# Camera.net
KiCad netlist of a schematic drawn in EAGLE
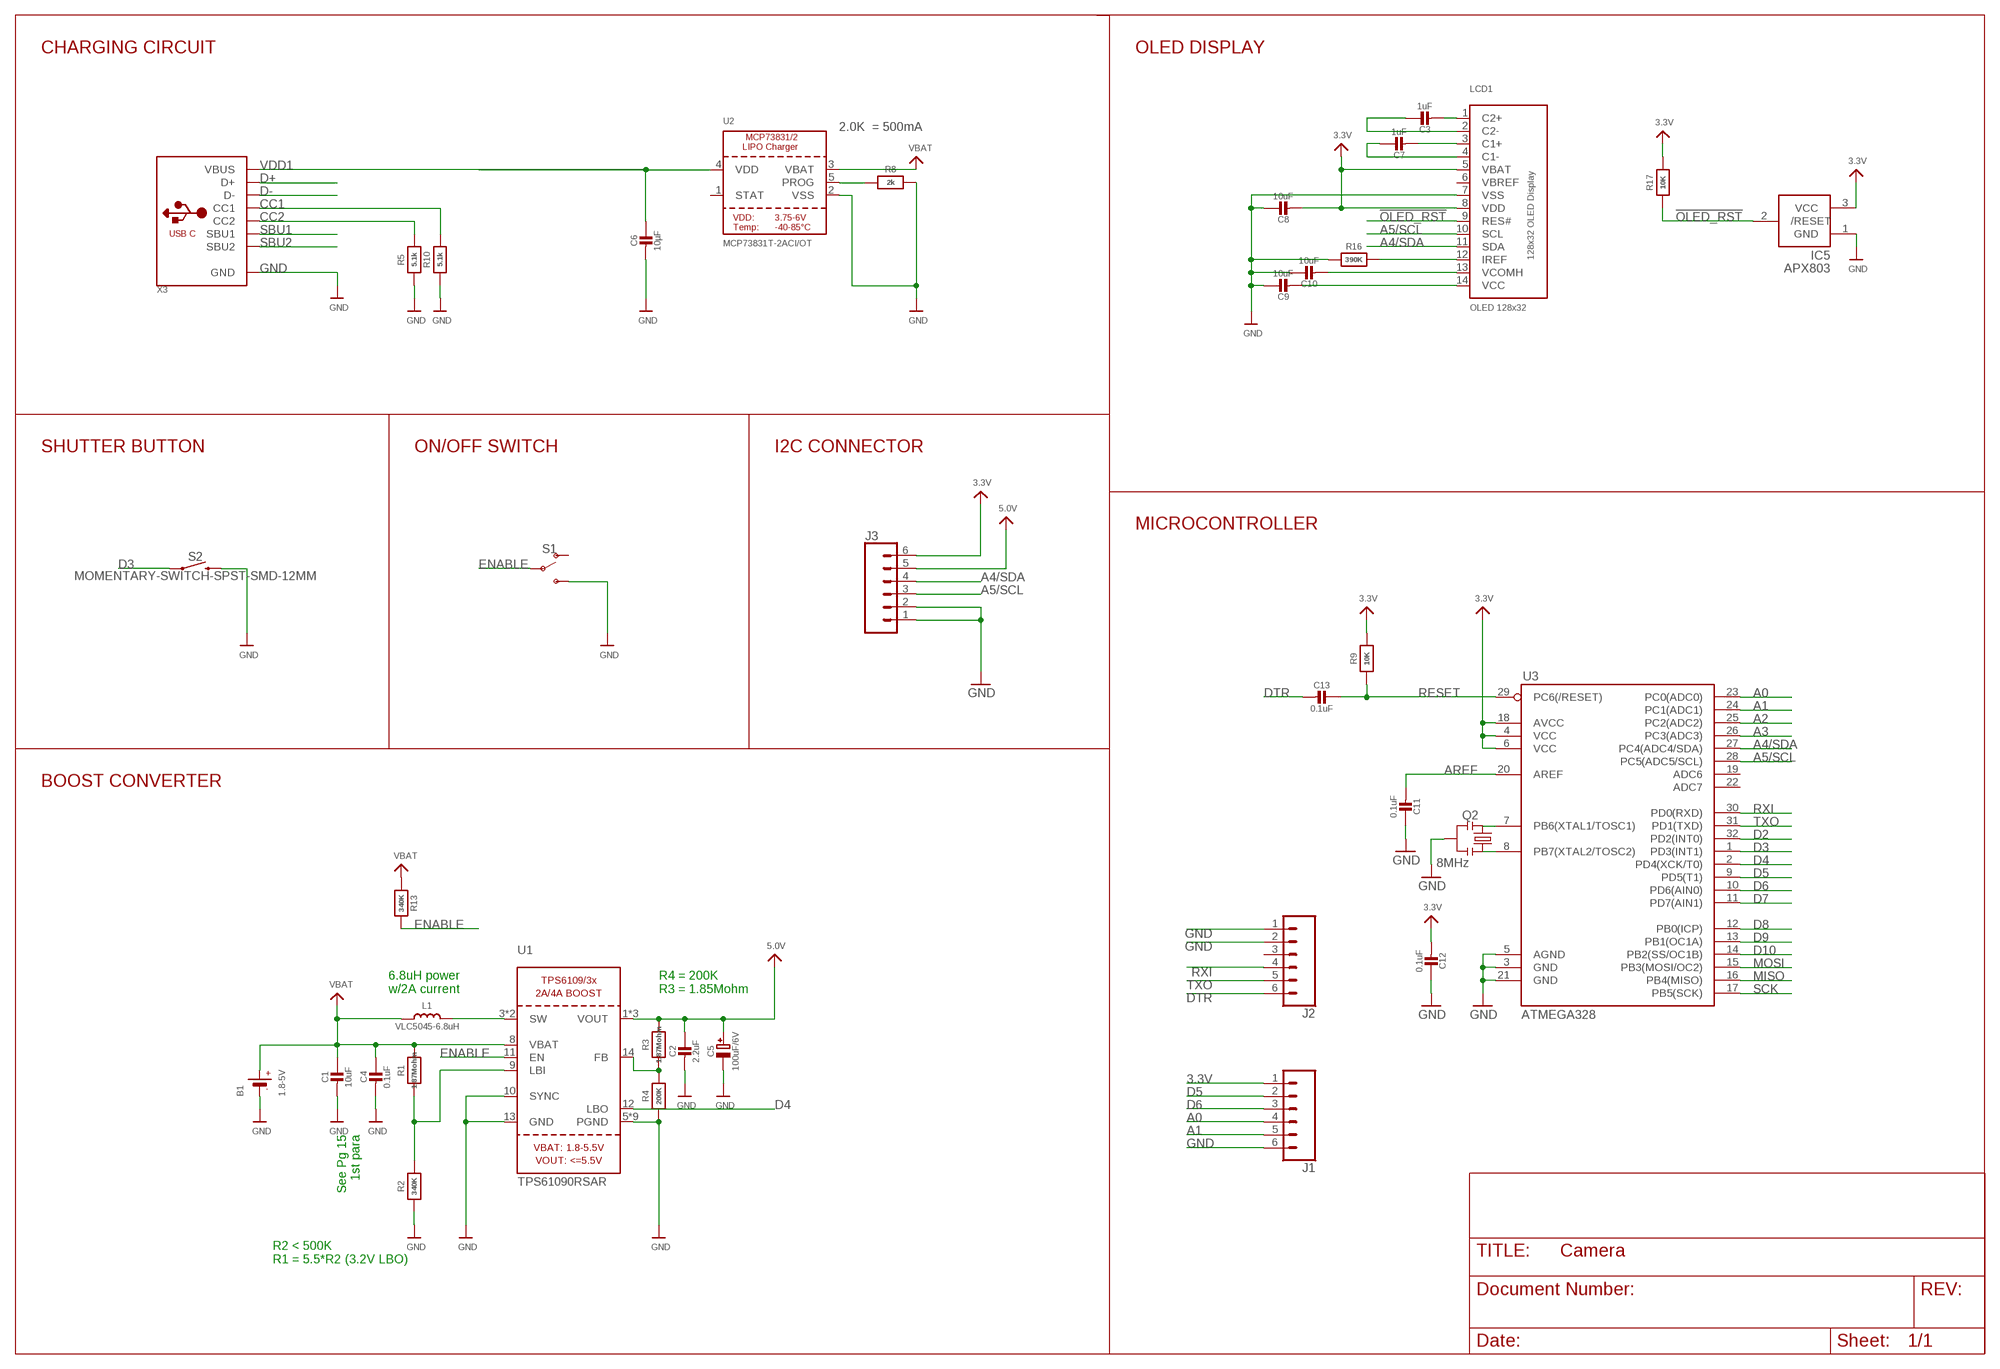
[diagram p0: schematic, sheet 1]

(export (version "E")
  (design (tool "Eeschema 10.0.6"))
  (components
    (comp (ref "B1")
      (value "1.8-5V")
      (footprint "eagle-import:JSTPH2")
      (libsource (lib "eagle-import") (part "BATTERY"))
    )
    (comp (ref "C1")
      (value "10uF")
      (footprint "eagle-import:0805-NO")
      (libsource (lib "eagle-import") (part "CAP_CERAMIC0805-NOOUTLINE"))
    )
    (comp (ref "C2")
      (value "2.2uF")
      (footprint "eagle-import:0805-NO")
      (libsource (lib "eagle-import") (part "CAP_CERAMIC0805-NOOUTLINE"))
    )
    (comp (ref "C3")
      (value "1uF")
      (footprint "eagle-import:0805-NO")
      (libsource (lib "eagle-import") (part "CAP_CERAMIC0805-NOOUTLINE"))
    )
    (comp (ref "C4")
      (value "0.1uF")
      (footprint "eagle-import:0805-NO")
      (libsource (lib "eagle-import") (part "CAP_CERAMIC0805-NOOUTLINE"))
    )
    (comp (ref "C5")
      (value "100uF/6V")
      (footprint "eagle-import:EIA3528-21_B-R")
      (libsource (lib "eagle-import") (part "CAP_TANTALUMB/3528_REFLOW"))
    )
    (comp (ref "C6")
      (value "10µF")
      (footprint "eagle-import:0805-NO")
      (libsource (lib "eagle-import") (part "CAP_CERAMIC0805-NOOUTLINE"))
    )
    (comp (ref "C7")
      (value "1uF")
      (footprint "eagle-import:0805-NO")
      (libsource (lib "eagle-import") (part "CAP_CERAMIC0805-NOOUTLINE"))
    )
    (comp (ref "C8")
      (value "10uF")
      (footprint "eagle-import:0805-NO")
      (libsource (lib "eagle-import") (part "CAP_CERAMIC0805-NOOUTLINE"))
    )
    (comp (ref "C9")
      (value "10uF")
      (footprint "eagle-import:0805-NO")
      (libsource (lib "eagle-import") (part "CAP_CERAMIC0805-NOOUTLINE"))
    )
    (comp (ref "C10")
      (value "10uF")
      (footprint "eagle-import:0805-NO")
      (libsource (lib "eagle-import") (part "CAP_CERAMIC0805-NOOUTLINE"))
    )
    (comp (ref "C11")
      (value "0.1uF")
      (footprint "eagle-import:0805-NO")
      (libsource (lib "eagle-import") (part "CAP_CERAMIC0805-NOOUTLINE"))
    )
    (comp (ref "C12")
      (value "0.1uF")
      (footprint "eagle-import:0805-NO")
      (libsource (lib "eagle-import") (part "CAP_CERAMIC0805-NOOUTLINE"))
    )
    (comp (ref "C13")
      (value "0.1uF")
      (footprint "eagle-import:0805-NO")
      (libsource (lib "eagle-import") (part "CAP_CERAMIC0805-NOOUTLINE"))
    )
    (comp (ref "IC5")
      (value "APX803")
      (footprint "eagle-import:SOT23")
      (libsource (lib "eagle-import") (part "AXP083-SAG"))
    )
    (comp (ref "J1")
      (value "CONN_06SMD-FEMALE-V2")
      (footprint "eagle-import:1X06-SMD-FEMALE")
      (libsource (lib "eagle-import") (part "CONN_06SMD-FEMALE-V2"))
    )
    (comp (ref "J2")
      (value "CONN_06SMD-FEMALE-V2")
      (footprint "eagle-import:1X06-SMD-FEMALE")
      (libsource (lib "eagle-import") (part "CONN_06SMD-FEMALE-V2"))
    )
    (comp (ref "J3")
      (value "CONN_06SMD-FEMALE-V2")
      (footprint "eagle-import:1X06-SMD-FEMALE")
      (libsource (lib "eagle-import") (part "CONN_06SMD-FEMALE-V2"))
    )
    (comp (ref "L1")
      (value "VLC5045-6.8uH")
      (footprint "eagle-import:INDUCTOR_5X5MM_TDK_VLC5045")
      (libsource (lib "eagle-import") (part "INDUCTORTDK_VLC5045"))
    )
    (comp (ref "LCD1")
      (value "OLED 128x32")
      (footprint "eagle-import:UG-2832HSWEG02_WRAPUNDER")
      (libsource (lib "eagle-import") (part "DISP_OLED_UG-2832HSWEG02"))
    )
    (comp (ref "Q2")
      (value "8MHz")
      (footprint "eagle-import:RESONATOR-SMD")
      (libsource (lib "eagle-import") (part "RESONATORSMD"))
    )
    (comp (ref "R1")
      (value "1.87Mohm")
      (footprint "eagle-import:0805-NO")
      (libsource (lib "eagle-import") (part "RESISTOR0805_NOOUTLINE"))
    )
    (comp (ref "R2")
      (value "340K")
      (footprint "eagle-import:0805-NO")
      (libsource (lib "eagle-import") (part "RESISTOR0805_NOOUTLINE"))
    )
    (comp (ref "R3")
      (value "1.87Mohm")
      (footprint "eagle-import:0805-NO")
      (libsource (lib "eagle-import") (part "RESISTOR0805_NOOUTLINE"))
    )
    (comp (ref "R4")
      (value "200K")
      (footprint "eagle-import:0805-NO")
      (libsource (lib "eagle-import") (part "RESISTOR0805_NOOUTLINE"))
    )
    (comp (ref "R5")
      (value "5.1k")
      (footprint "eagle-import:0805-NO")
      (libsource (lib "eagle-import") (part "RESISTOR0805_NOOUTLINE"))
    )
    (comp (ref "R8")
      (value "2k")
      (footprint "eagle-import:0805-NO")
      (libsource (lib "eagle-import") (part "RESISTOR0805_NOOUTLINE"))
    )
    (comp (ref "R9")
      (value "10K")
      (footprint "eagle-import:0805-NO")
      (libsource (lib "eagle-import") (part "RESISTOR0805_NOOUTLINE"))
    )
    (comp (ref "R10")
      (value "5.1k")
      (footprint "eagle-import:0805-NO")
      (libsource (lib "eagle-import") (part "RESISTOR0805_NOOUTLINE"))
    )
    (comp (ref "R13")
      (value "340K")
      (footprint "eagle-import:0805-NO")
      (libsource (lib "eagle-import") (part "RESISTOR0805_NOOUTLINE"))
    )
    (comp (ref "R16")
      (value "390K")
      (footprint "eagle-import:0805-NO")
      (libsource (lib "eagle-import") (part "RESISTOR0805_NOOUTLINE"))
    )
    (comp (ref "R17")
      (value "10K")
      (footprint "eagle-import:0805-NO")
      (libsource (lib "eagle-import") (part "RESISTOR0805_NOOUTLINE"))
    )
    (comp (ref "S1")
      (value "SWITCH-SPDT-SMD-RIGHT-ANGLE")
      (footprint "eagle-import:SWITCH_SPST_SMD_A")
      (libsource (lib "eagle-import") (part "SWITCH-SPDT-SMD-RIGHT-ANGLE"))
    )
    (comp (ref "S2")
      (value "MOMENTARY-SWITCH-SPST-SMD-12MM")
      (footprint "eagle-import:TACTILE_SWITCH_SMD_12MM")
      (libsource (lib "eagle-import") (part "MOMENTARY-SWITCH-SPST-SMD-12MM"))
    )
    (comp (ref "U1")
      (value "TPS61090RSAR")
      (footprint "eagle-import:PVQFN-16")
      (libsource (lib "eagle-import") (part "VREG_TPS6103X"))
    )
    (comp (ref "U2")
      (value "MCP73831T-2ACI/OT")
      (footprint "eagle-import:SOT23-5")
      (libsource (lib "eagle-import") (part "MCP73831/2"))
    )
    (comp (ref "U3")
      (value "ATMEGA328")
      (footprint "eagle-import:TQFP32-08")
      (libsource (lib "eagle-import") (part "ATMEGA168"))
    )
    (comp (ref "X3")
      (value "USB_C")
      (footprint "eagle-import:USB_C_CUSB31-CFM2AX-01-X")
      (libsource (lib "eagle-import") (part "USB_C"))
    )
  )
  (nets
    (net (code "1") (name "/A0") (class "Default")
      (node (ref "J1") (pin "4") (pinfunction "4_4") (pintype "passive"))
      (node (ref "U3") (pin "23") (pinfunction "PC0(ADC0)_23") (pintype "bidirectional"))
    )
    (net (code "2") (name "/A1") (class "Default")
      (node (ref "J1") (pin "5") (pinfunction "5_5") (pintype "passive"))
      (node (ref "U3") (pin "24") (pinfunction "PC1(ADC1)_24") (pintype "bidirectional"))
    )
    (net (code "3") (name "/A2") (class "Default")
      (node (ref "U3") (pin "25") (pinfunction "PC2(ADC2)_25") (pintype "bidirectional"))
    )
    (net (code "4") (name "/A3") (class "Default")
      (node (ref "U3") (pin "26") (pinfunction "PC3(ADC3)_26") (pintype "bidirectional"))
    )
    (net (code "5") (name "/A4{slash}SDA") (class "Default")
      (node (ref "J3") (pin "4") (pinfunction "4_4") (pintype "passive"))
      (node (ref "LCD1") (pin "11") (pinfunction "SDA_11") (pintype "bidirectional"))
      (node (ref "U3") (pin "27") (pinfunction "PC4(ADC4/SDA)_27") (pintype "bidirectional"))
    )
    (net (code "6") (name "/A5{slash}SCL") (class "Default")
      (node (ref "J3") (pin "3") (pinfunction "3_3") (pintype "passive"))
      (node (ref "LCD1") (pin "10") (pinfunction "SCL_10") (pintype "bidirectional"))
      (node (ref "U3") (pin "28") (pinfunction "PC5(ADC5/SCL)_28") (pintype "bidirectional"))
    )
    (net (code "7") (name "/AREF") (class "Default")
      (node (ref "C11") (pin "2") (pinfunction "2_2") (pintype "passive"))
      (node (ref "U3") (pin "20") (pinfunction "AREF_20") (pintype "bidirectional"))
    )
    (net (code "8") (name "/CC1") (class "Default")
      (node (ref "R10") (pin "2") (pinfunction "2_2") (pintype "passive"))
      (node (ref "X3") (pin "A5") (pinfunction "CC1_A5") (pintype "bidirectional"))
    )
    (net (code "9") (name "/CC2") (class "Default")
      (node (ref "R5") (pin "2") (pinfunction "2_2") (pintype "passive"))
      (node (ref "X3") (pin "B5") (pinfunction "CC2_B5") (pintype "bidirectional"))
    )
    (net (code "10") (name "/D+") (class "Default")
      (node (ref "X3") (pin "A6") (pinfunction "D+_A6") (pintype "bidirectional"))
      (node (ref "X3") (pin "B6") (pinfunction "D+_B6") (pintype "bidirectional"))
    )
    (net (code "11") (name "/D-") (class "Default")
      (node (ref "X3") (pin "A7") (pinfunction "D-_A7") (pintype "bidirectional"))
      (node (ref "X3") (pin "B7") (pinfunction "D-_B7") (pintype "bidirectional"))
    )
    (net (code "12") (name "/D2") (class "Default")
      (node (ref "U3") (pin "32") (pinfunction "PD2(INT0)_32") (pintype "bidirectional"))
    )
    (net (code "13") (name "/D3") (class "Default")
      (node (ref "S2") (pin "1") (pinfunction "1_1") (pintype "passive"))
      (node (ref "U3") (pin "1") (pinfunction "PD3(INT1)_1") (pintype "bidirectional"))
    )
    (net (code "14") (name "/D4") (class "Default")
      (node (ref "U1") (pin "12") (pinfunction "LBO_12") (pintype "output"))
      (node (ref "U3") (pin "2") (pinfunction "PD4(XCK/T0)_2") (pintype "bidirectional"))
    )
    (net (code "15") (name "/D5") (class "Default")
      (node (ref "J1") (pin "2") (pinfunction "2_2") (pintype "passive"))
      (node (ref "U3") (pin "9") (pinfunction "PD5(T1)_9") (pintype "bidirectional"))
    )
    (net (code "16") (name "/D6") (class "Default")
      (node (ref "J1") (pin "3") (pinfunction "3_3") (pintype "passive"))
      (node (ref "U3") (pin "10") (pinfunction "PD6(AIN0)_10") (pintype "bidirectional"))
    )
    (net (code "17") (name "/D7") (class "Default")
      (node (ref "U3") (pin "11") (pinfunction "PD7(AIN1)_11") (pintype "bidirectional"))
    )
    (net (code "18") (name "/D8") (class "Default")
      (node (ref "U3") (pin "12") (pinfunction "PB0(ICP)_12") (pintype "bidirectional"))
    )
    (net (code "19") (name "/D9") (class "Default")
      (node (ref "U3") (pin "13") (pinfunction "PB1(OC1A)_13") (pintype "bidirectional"))
    )
    (net (code "20") (name "/D10") (class "Default")
      (node (ref "U3") (pin "14") (pinfunction "PB2(SS/OC1B)_14") (pintype "bidirectional"))
    )
    (net (code "21") (name "/DTR") (class "Default")
      (node (ref "C13") (pin "2") (pinfunction "2_2") (pintype "passive"))
      (node (ref "J2") (pin "6") (pinfunction "6_6") (pintype "passive"))
    )
    (net (code "22") (name "/ENABLE") (class "Default")
      (node (ref "R13") (pin "2") (pinfunction "2_2") (pintype "passive"))
      (node (ref "S1") (pin "2") (pinfunction "P_2") (pintype "passive"))
      (node (ref "U1") (pin "11") (pinfunction "EN_11") (pintype "input"))
    )
    (net (code "23") (name "/MISO") (class "Default")
      (node (ref "U3") (pin "16") (pinfunction "PB4(MISO)_16") (pintype "bidirectional"))
    )
    (net (code "24") (name "/MOSI") (class "Default")
      (node (ref "U3") (pin "15") (pinfunction "PB3(MOSI/OC2)_15") (pintype "bidirectional"))
    )
    (net (code "25") (name "/RESET") (class "Default")
      (node (ref "C13") (pin "1") (pinfunction "1_1") (pintype "passive"))
      (node (ref "R9") (pin "1") (pinfunction "1_1") (pintype "passive"))
      (node (ref "U3") (pin "29") (pinfunction "PC6(/RESET)_29") (pintype "bidirectional"))
    )
    (net (code "26") (name "/RXI") (class "Default")
      (node (ref "J2") (pin "4") (pinfunction "4_4") (pintype "passive"))
      (node (ref "U3") (pin "30") (pinfunction "PD0(RXD)_30") (pintype "bidirectional"))
    )
    (net (code "27") (name "/SBU1") (class "Default")
      (node (ref "X3") (pin "A8") (pinfunction "SBU1_A8") (pintype "bidirectional"))
    )
    (net (code "28") (name "/SBU2") (class "Default")
      (node (ref "X3") (pin "B8") (pinfunction "SBU2_B8") (pintype "bidirectional"))
    )
    (net (code "29") (name "/SCK") (class "Default")
      (node (ref "U3") (pin "17") (pinfunction "PB5(SCK)_17") (pintype "bidirectional"))
    )
    (net (code "30") (name "/TXO") (class "Default")
      (node (ref "J2") (pin "5") (pinfunction "5_5") (pintype "passive"))
      (node (ref "U3") (pin "31") (pinfunction "PD1(TXD)_31") (pintype "bidirectional"))
    )
    (net (code "31") (name "/VBREF") (class "Default")
      (node (ref "LCD1") (pin "6") (pinfunction "VBREF_6") (pintype "power_in"))
    )
    (net (code "32") (name "/VDD1") (class "Default")
      (node (ref "C6") (pin "1") (pinfunction "1_1") (pintype "passive"))
      (node (ref "U2") (pin "4") (pinfunction "VDD_4") (pintype "power_in"))
      (node (ref "X3") (pin "A4B9") (pinfunction "VBUS_A4B9") (pintype "power_in"))
      (node (ref "X3") (pin "B4A9") (pinfunction "VBUS_B4A9") (pintype "power_in"))
    )
    (net (code "33") (name "/~{OLED_RST}") (class "Default")
      (node (ref "IC5") (pin "2") (pinfunction "/RESET_2") (pintype "output"))
      (node (ref "LCD1") (pin "9") (pinfunction "RES#_9") (pintype "bidirectional"))
      (node (ref "R17") (pin "1") (pinfunction "1_1") (pintype "passive"))
    )
    (net (code "34") (name "3.3V") (class "Default")
      (node (ref "C12") (pin "2") (pinfunction "2_2") (pintype "passive"))
      (node (ref "C8") (pin "2") (pinfunction "2_2") (pintype "passive"))
      (node (ref "IC5") (pin "3") (pinfunction "VCC_3") (pintype "power_in"))
      (node (ref "J1") (pin "1") (pinfunction "1_1") (pintype "passive"))
      (node (ref "J3") (pin "6") (pinfunction "6_6") (pintype "passive"))
      (node (ref "LCD1") (pin "5") (pinfunction "VBAT_5") (pintype "power_in"))
      (node (ref "LCD1") (pin "8") (pinfunction "VDD_8") (pintype "power_in"))
      (node (ref "R17") (pin "2") (pinfunction "2_2") (pintype "passive"))
      (node (ref "R9") (pin "2") (pinfunction "2_2") (pintype "passive"))
      (node (ref "U3") (pin "18") (pinfunction "AVCC_18") (pintype "bidirectional"))
      (node (ref "U3") (pin "4") (pinfunction "VCC_4") (pintype "bidirectional"))
      (node (ref "U3") (pin "6") (pinfunction "VCC_6") (pintype "bidirectional"))
    )
    (net (code "35") (name "5.0V") (class "Default")
      (node (ref "C2") (pin "1") (pinfunction "1_1") (pintype "passive"))
      (node (ref "C5") (pin "+") (pinfunction "+_+") (pintype "passive"))
      (node (ref "J3") (pin "5") (pinfunction "5_5") (pintype "passive"))
      (node (ref "R3") (pin "2") (pinfunction "2_2") (pintype "passive"))
      (node (ref "U1") (pin "1") (pinfunction "VOUT_1") (pintype "power_in"))
      (node (ref "U1") (pin "15") (pinfunction "VOUT_15") (pintype "power_in"))
      (node (ref "U1") (pin "16") (pinfunction "VOUT_16") (pintype "power_in"))
    )
    (net (code "36") (name "GND") (class "Default")
      (node (ref "B1") (pin "1") (pinfunction "-_1") (pintype "passive"))
      (node (ref "C1") (pin "2") (pinfunction "2_2") (pintype "passive"))
      (node (ref "C10") (pin "1") (pinfunction "1_1") (pintype "passive"))
      (node (ref "C11") (pin "1") (pinfunction "1_1") (pintype "passive"))
      (node (ref "C12") (pin "1") (pinfunction "1_1") (pintype "passive"))
      (node (ref "C2") (pin "2") (pinfunction "2_2") (pintype "passive"))
      (node (ref "C4") (pin "2") (pinfunction "2_2") (pintype "passive"))
      (node (ref "C5") (pin "-") (pinfunction "-_-") (pintype "passive"))
      (node (ref "C6") (pin "2") (pinfunction "2_2") (pintype "passive"))
      (node (ref "C8") (pin "1") (pinfunction "1_1") (pintype "passive"))
      (node (ref "C9") (pin "1") (pinfunction "1_1") (pintype "passive"))
      (node (ref "IC5") (pin "1") (pinfunction "GND_1") (pintype "power_in"))
      (node (ref "J1") (pin "6") (pinfunction "6_6") (pintype "passive"))
      (node (ref "J2") (pin "1") (pinfunction "1_1") (pintype "passive"))
      (node (ref "J2") (pin "2") (pinfunction "2_2") (pintype "passive"))
      (node (ref "J3") (pin "1") (pinfunction "1_1") (pintype "passive"))
      (node (ref "J3") (pin "2") (pinfunction "2_2") (pintype "passive"))
      (node (ref "LCD1") (pin "7") (pinfunction "VSS_7") (pintype "power_in"))
      (node (ref "Q2") (pin "2") (pinfunction "2_2") (pintype "passive"))
      (node (ref "R10") (pin "1") (pinfunction "1_1") (pintype "passive"))
      (node (ref "R16") (pin "1") (pinfunction "1_1") (pintype "passive"))
      (node (ref "R2") (pin "1") (pinfunction "1_1") (pintype "passive"))
      (node (ref "R4") (pin "1") (pinfunction "1_1") (pintype "passive"))
      (node (ref "R5") (pin "1") (pinfunction "1_1") (pintype "passive"))
      (node (ref "R8") (pin "2") (pinfunction "2_2") (pintype "passive"))
      (node (ref "S1") (pin "3") (pinfunction "S_3") (pintype "passive"))
      (node (ref "S2") (pin "3") (pinfunction "2_3") (pintype "passive"))
      (node (ref "U1") (pin "10") (pinfunction "SYNC_10") (pintype "input"))
      (node (ref "U1") (pin "13") (pinfunction "GND_13") (pintype "power_in"))
      (node (ref "U1") (pin "5") (pinfunction "PGND_5") (pintype "power_in"))
      (node (ref "U1") (pin "6") (pinfunction "PGND_6") (pintype "power_in"))
      (node (ref "U1") (pin "7") (pinfunction "PGND_7") (pintype "power_in"))
      (node (ref "U1") (pin "P$18") (pinfunction "PGND_P$18") (pintype "power_in"))
      (node (ref "U1") (pin "P$19") (pinfunction "PGND_P$19") (pintype "power_in"))
      (node (ref "U1") (pin "P$20") (pinfunction "PGND_P$20") (pintype "power_in"))
      (node (ref "U1") (pin "P$21") (pinfunction "PGND_P$21") (pintype "power_in"))
      (node (ref "U1") (pin "P$22") (pinfunction "PGND_P$22") (pintype "power_in"))
      (node (ref "U1") (pin "THERMAL") (pinfunction "PGND_THERMAL") (pintype "power_in"))
      (node (ref "U2") (pin "2") (pinfunction "VSS_2") (pintype "power_in"))
      (node (ref "U3") (pin "21") (pinfunction "GND_21") (pintype "bidirectional"))
      (node (ref "U3") (pin "3") (pinfunction "GND_3") (pintype "bidirectional"))
      (node (ref "U3") (pin "5") (pinfunction "AGND_5") (pintype "bidirectional"))
      (node (ref "X3") (pin "A1B12") (pinfunction "GND_A1B12") (pintype "power_in"))
      (node (ref "X3") (pin "B1A12") (pinfunction "GND_B1A12") (pintype "power_in"))
    )
    (net (code "37") (name "Net-(L1-2)") (class "Default")
      (node (ref "L1") (pin "P$2") (pinfunction "2_P$2") (pintype "passive"))
      (node (ref "U1") (pin "3") (pinfunction "SW_3") (pintype "input"))
      (node (ref "U1") (pin "4") (pinfunction "SW_4") (pintype "input"))
    )
    (net (code "38") (name "Net-(LCD1-C1+)") (class "Default")
      (node (ref "C7") (pin "2") (pinfunction "2_2") (pintype "passive"))
      (node (ref "LCD1") (pin "3") (pinfunction "C1+_3") (pintype "bidirectional"))
    )
    (net (code "39") (name "Net-(LCD1-C1-)") (class "Default")
      (node (ref "C7") (pin "1") (pinfunction "1_1") (pintype "passive"))
      (node (ref "LCD1") (pin "4") (pinfunction "C1-_4") (pintype "bidirectional"))
    )
    (net (code "40") (name "Net-(LCD1-C2+)") (class "Default")
      (node (ref "C3") (pin "2") (pinfunction "2_2") (pintype "passive"))
      (node (ref "LCD1") (pin "1") (pinfunction "C2+_1") (pintype "bidirectional"))
    )
    (net (code "41") (name "Net-(LCD1-C2-)") (class "Default")
      (node (ref "C3") (pin "1") (pinfunction "1_1") (pintype "passive"))
      (node (ref "LCD1") (pin "2") (pinfunction "C2-_2") (pintype "bidirectional"))
    )
    (net (code "42") (name "Net-(LCD1-IREF)") (class "Default")
      (node (ref "LCD1") (pin "12") (pinfunction "IREF_12") (pintype "bidirectional"))
      (node (ref "R16") (pin "2") (pinfunction "2_2") (pintype "passive"))
    )
    (net (code "43") (name "Net-(LCD1-VCC)") (class "Default")
      (node (ref "C9") (pin "2") (pinfunction "2_2") (pintype "passive"))
      (node (ref "LCD1") (pin "14") (pinfunction "VCC_14") (pintype "power_in"))
    )
    (net (code "44") (name "Net-(LCD1-VCOMH)") (class "Default")
      (node (ref "C10") (pin "2") (pinfunction "2_2") (pintype "passive"))
      (node (ref "LCD1") (pin "13") (pinfunction "VCOMH_13") (pintype "power_in"))
    )
    (net (code "45") (name "Net-(U1-FB)") (class "Default")
      (node (ref "R3") (pin "1") (pinfunction "1_1") (pintype "passive"))
      (node (ref "R4") (pin "2") (pinfunction "2_2") (pintype "passive"))
      (node (ref "U1") (pin "14") (pinfunction "FB_14") (pintype "input"))
    )
    (net (code "46") (name "Net-(U1-LBI)") (class "Default")
      (node (ref "R1") (pin "1") (pinfunction "1_1") (pintype "passive"))
      (node (ref "R2") (pin "2") (pinfunction "2_2") (pintype "passive"))
      (node (ref "U1") (pin "9") (pinfunction "LBI_9") (pintype "input"))
    )
    (net (code "47") (name "Net-(U2-PROG)") (class "Default")
      (node (ref "R8") (pin "1") (pinfunction "1_1") (pintype "passive"))
      (node (ref "U2") (pin "5") (pinfunction "PROG_5") (pintype "input"))
    )
    (net (code "48") (name "Net-(U3-PB6(XTAL1{slash}TOSC1))") (class "Default")
      (node (ref "Q2") (pin "3") (pinfunction "3_3") (pintype "passive"))
      (node (ref "U3") (pin "7") (pinfunction "PB6(XTAL1/TOSC1)_7") (pintype "bidirectional"))
    )
    (net (code "49") (name "Net-(U3-PB7(XTAL2{slash}TOSC2))") (class "Default")
      (node (ref "Q2") (pin "1") (pinfunction "1_1") (pintype "passive"))
      (node (ref "U3") (pin "8") (pinfunction "PB7(XTAL2/TOSC2)_8") (pintype "bidirectional"))
    )
    (net (code "50") (name "VBAT") (class "Default")
      (node (ref "B1") (pin "2") (pinfunction "+_2") (pintype "passive"))
      (node (ref "C1") (pin "1") (pinfunction "1_1") (pintype "passive"))
      (node (ref "C4") (pin "1") (pinfunction "1_1") (pintype "passive"))
      (node (ref "L1") (pin "P$1") (pinfunction "1_P$1") (pintype "passive"))
      (node (ref "R1") (pin "2") (pinfunction "2_2") (pintype "passive"))
      (node (ref "R13") (pin "1") (pinfunction "1_1") (pintype "passive"))
      (node (ref "U1") (pin "8") (pinfunction "VBAT_8") (pintype "input"))
      (node (ref "U2") (pin "3") (pinfunction "VBAT_3") (pintype "power_in"))
    )
    (net (code "51") (name "unconnected-(J2-Pad3)") (class "Default")
      (node (ref "J2") (pin "3") (pinfunction "3_3") (pintype "passive"))
    )
    (net (code "52") (name "unconnected-(S1-O-Pad1)") (class "Default")
      (node (ref "S1") (pin "1") (pinfunction "O_1") (pintype "passive"))
    )
    (net (code "53") (name "unconnected-(U2-STAT-Pad1)") (class "Default")
      (node (ref "U2") (pin "1") (pinfunction "STAT_1") (pintype "output"))
    )
    (net (code "54") (name "unconnected-(U3-ADC6-Pad19)") (class "Default")
      (node (ref "U3") (pin "19") (pinfunction "ADC6_19") (pintype "bidirectional"))
    )
    (net (code "55") (name "unconnected-(U3-ADC7-Pad22)") (class "Default")
      (node (ref "U3") (pin "22") (pinfunction "ADC7_22") (pintype "bidirectional"))
    )
  )
)
